# ethernetGateway.net
KiCad netlist of a schematic drawn in EAGLE
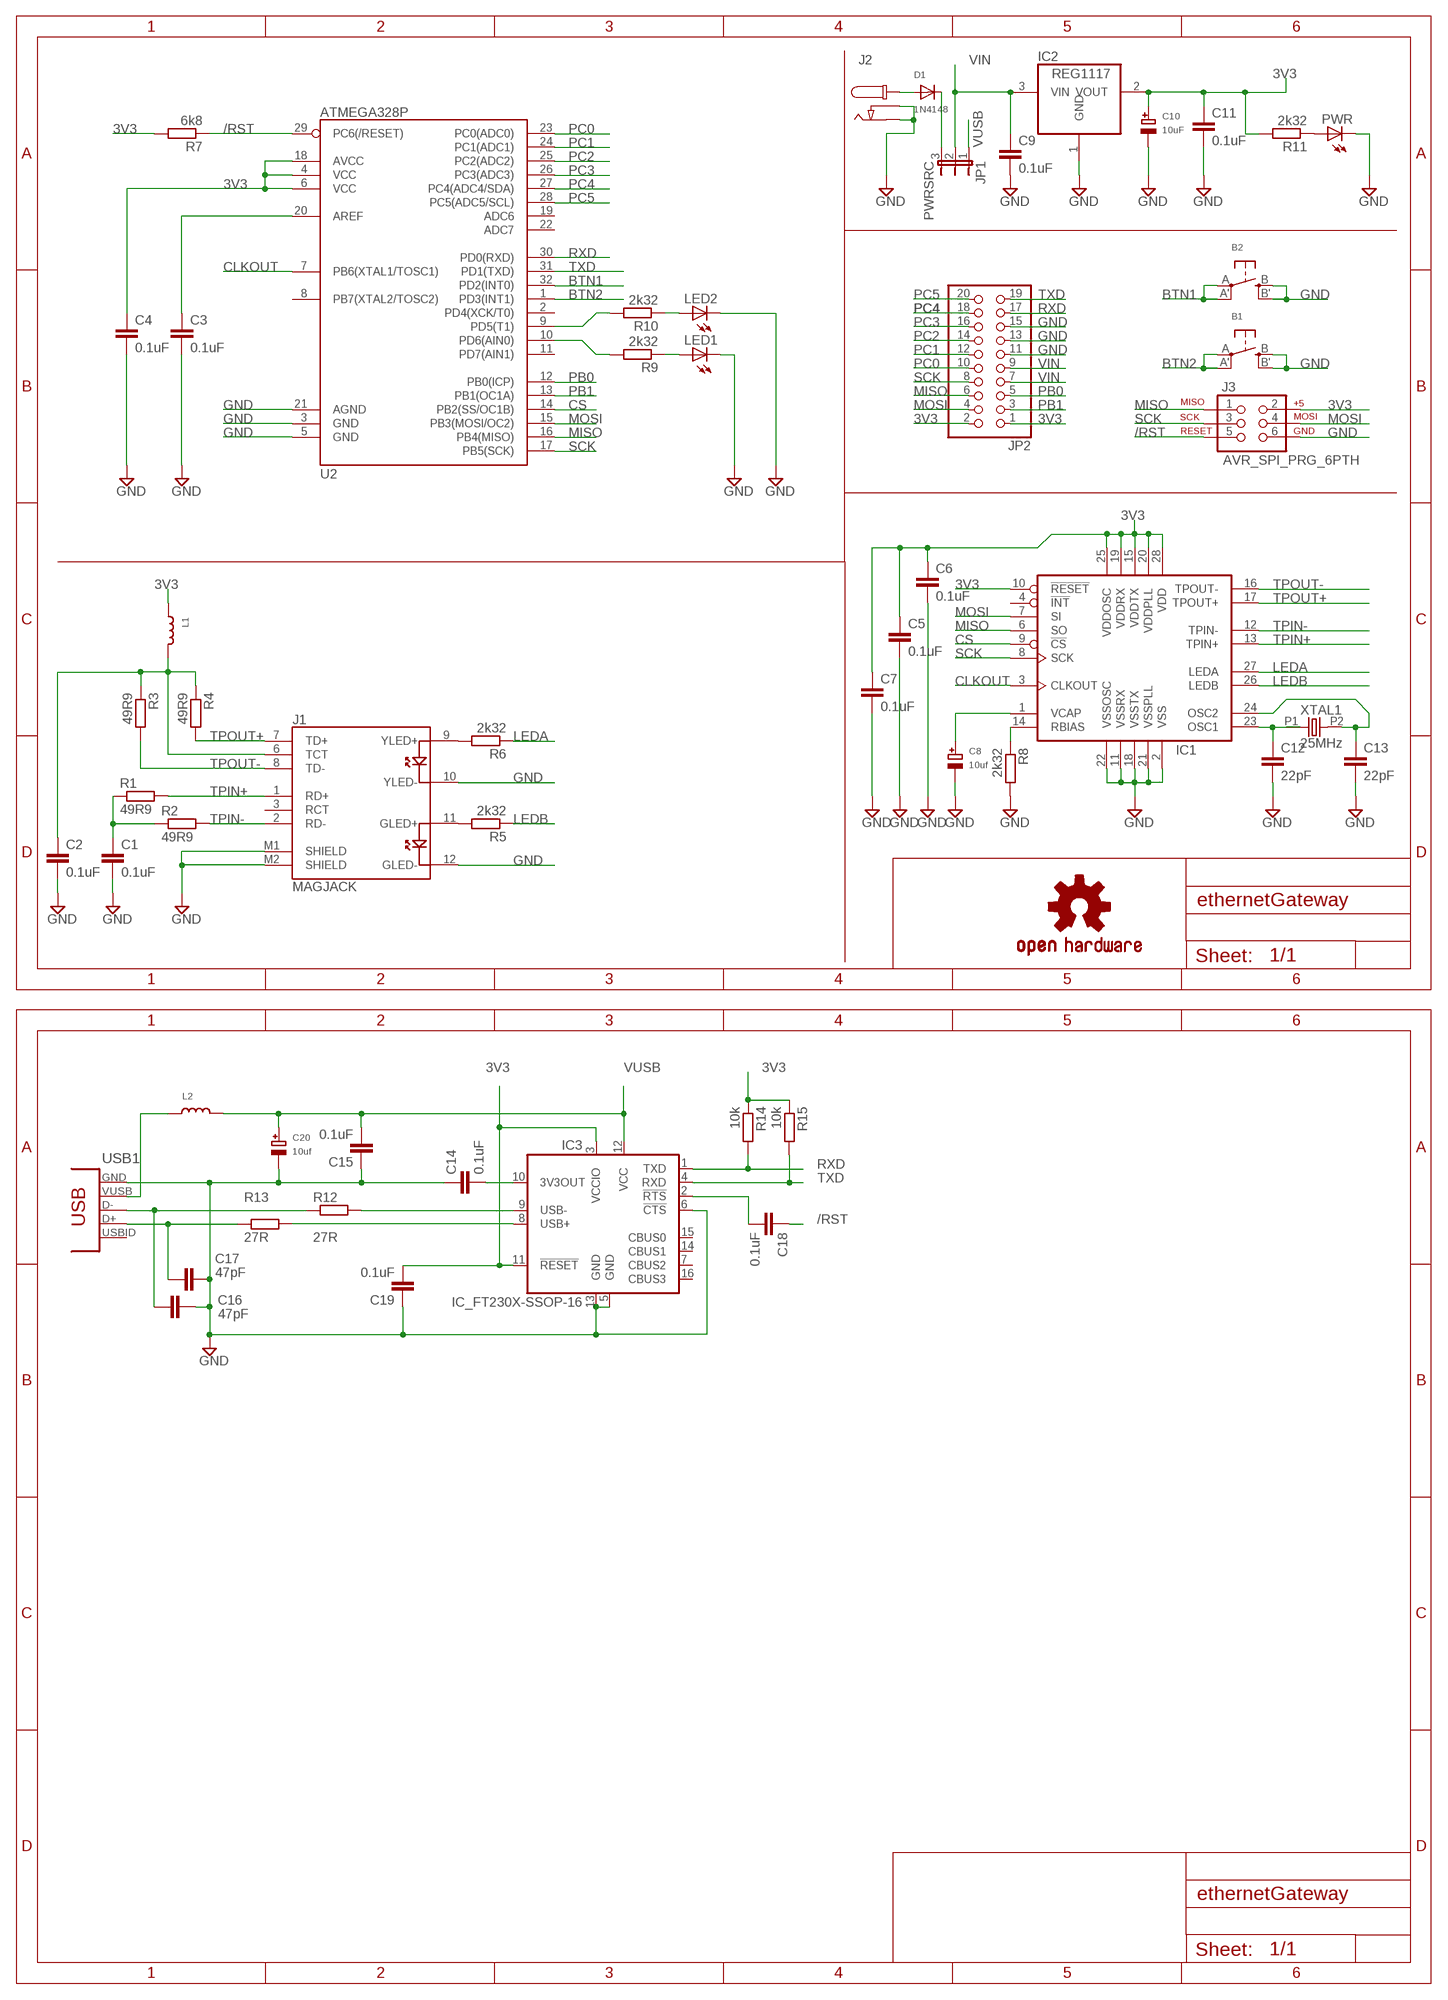
[diagram p0: schematic, sheet 1]

(export (version "E")
  (design (tool "Eeschema 10.0.6"))
  (components
    (comp (ref "B1")
      (value "SWITCH_TACT_SMT4.6X2.8")
      (footprint "eagle-import:BTN_KMR2_4.6X2.8")
      (libsource (lib "eagle-import") (part "SWITCH_TACT_SMT4.6X2.8"))
    )
    (comp (ref "B2")
      (value "SWITCH_TACT_SMT4.6X2.8")
      (footprint "eagle-import:BTN_KMR2_4.6X2.8")
      (libsource (lib "eagle-import") (part "SWITCH_TACT_SMT4.6X2.8"))
    )
    (comp (ref "C1")
      (value "0.1uF")
      (footprint "eagle-import:C0805")
      (libsource (lib "eagle-import") (part "C-EUC0805"))
    )
    (comp (ref "C2")
      (value "0.1uF")
      (footprint "eagle-import:C0805")
      (libsource (lib "eagle-import") (part "C-EUC0805"))
    )
    (comp (ref "C3")
      (value "0.1uF")
      (footprint "eagle-import:C0805")
      (libsource (lib "eagle-import") (part "C-EUC0805"))
    )
    (comp (ref "C4")
      (value "0.1uF")
      (footprint "eagle-import:C0805")
      (libsource (lib "eagle-import") (part "C-EUC0805"))
    )
    (comp (ref "C5")
      (value "0.1uF")
      (footprint "eagle-import:C0805")
      (libsource (lib "eagle-import") (part "C-EUC0805"))
    )
    (comp (ref "C6")
      (value "0.1uF")
      (footprint "eagle-import:C0805")
      (libsource (lib "eagle-import") (part "C-EUC0805"))
    )
    (comp (ref "C7")
      (value "0.1uF")
      (footprint "eagle-import:C0805")
      (libsource (lib "eagle-import") (part "C-EUC0805"))
    )
    (comp (ref "C8")
      (value "10uf")
      (footprint "eagle-import:EIA7343-31_D-R")
      (libsource (lib "eagle-import") (part "CAP_TANTALUMD/7343_REFLOW"))
    )
    (comp (ref "C9")
      (value "0.1uF")
      (footprint "eagle-import:C0805")
      (libsource (lib "eagle-import") (part "C-EUC0805"))
    )
    (comp (ref "C10")
      (value "10uF")
      (footprint "eagle-import:EIA7343-31_D-R")
      (libsource (lib "eagle-import") (part "CAP_TANTALUMD/7343_REFLOW"))
    )
    (comp (ref "C11")
      (value "0.1uF")
      (footprint "eagle-import:C0805")
      (libsource (lib "eagle-import") (part "C-EUC0805"))
    )
    (comp (ref "C12")
      (value "22pF")
      (footprint "eagle-import:C0805")
      (libsource (lib "eagle-import") (part "C-EUC0805"))
    )
    (comp (ref "C13")
      (value "22pF")
      (footprint "eagle-import:C0805")
      (libsource (lib "eagle-import") (part "C-EUC0805"))
    )
    (comp (ref "C14")
      (value "0.1uF")
      (footprint "eagle-import:C0805")
      (libsource (lib "eagle-import") (part "C-EUC0805"))
    )
    (comp (ref "C15")
      (value "0.1uF")
      (footprint "eagle-import:C0805")
      (libsource (lib "eagle-import") (part "C-EUC0805"))
    )
    (comp (ref "C16")
      (value "47pF")
      (footprint "eagle-import:C0805")
      (libsource (lib "eagle-import") (part "C-EUC0805"))
    )
    (comp (ref "C17")
      (value "47pF")
      (footprint "eagle-import:C0805")
      (libsource (lib "eagle-import") (part "C-EUC0805"))
    )
    (comp (ref "C18")
      (value "0.1uF")
      (footprint "eagle-import:C0805")
      (libsource (lib "eagle-import") (part "C-EUC0805"))
    )
    (comp (ref "C19")
      (value "0.1uF")
      (footprint "eagle-import:C0805")
      (libsource (lib "eagle-import") (part "C-EUC0805"))
    )
    (comp (ref "C20")
      (value "10uf")
      (footprint "eagle-import:EIA7343-31_D-R")
      (libsource (lib "eagle-import") (part "CAP_TANTALUMD/7343_REFLOW"))
    )
    (comp (ref "D1")
      (value "1N4148")
      (footprint "eagle-import:SMADIODE")
      (libsource (lib "eagle-import") (part "DIODESMA"))
    )
    (comp (ref "IC1")
      (value "IC_ENC28J60-SOIC-28")
      (footprint "eagle-import:SOIC-28W")
      (libsource (lib "eagle-import") (part "IC_ENC28J60-SOIC-28"))
    )
    (comp (ref "IC2")
      (value "REG1117")
      (footprint "eagle-import:SOT223")
      (libsource (lib "eagle-import") (part "REG1117"))
    )
    (comp (ref "IC3")
      (value "IC_FT230X-SSOP-16")
      (footprint "eagle-import:SSOP-16-FTDI")
      (libsource (lib "eagle-import") (part "IC_FT230X-SSOP-16"))
    )
    (comp (ref "J1")
      (value "MAGJACK")
      (footprint "eagle-import:MAGJACK")
      (libsource (lib "eagle-import") (part "MAGJACK"))
    )
    (comp (ref "J2")
      (value "CON_DC_M-DC_PTH")
      (footprint "eagle-import:DC_BARREL_JACK_PTH_2MM")
      (libsource (lib "eagle-import") (part "CON_DC_M-DC_PTH"))
    )
    (comp (ref "J3")
      (value "AVR_SPI_PRG_6PTH")
      (footprint "eagle-import:2X3")
      (libsource (lib "eagle-import") (part "AVR_SPI_PRG_6PTH"))
    )
    (comp (ref "JP1")
      (value "PWRSRC")
      (footprint "eagle-import:JP2W")
      (libsource (lib "eagle-import") (part "JP2W"))
    )
    (comp (ref "JP2")
      (value "PINHD-2X10")
      (footprint "eagle-import:2X10")
      (libsource (lib "eagle-import") (part "PINHD-2X10"))
    )
    (comp (ref "L1")
      (value "INDUCTOR0805")
      (footprint "eagle-import:0805")
      (libsource (lib "eagle-import") (part "INDUCTOR0805"))
    )
    (comp (ref "L2")
      (value "INDUCTOR0805")
      (footprint "eagle-import:0805")
      (libsource (lib "eagle-import") (part "INDUCTOR0805"))
    )
    (comp (ref "LED1")
      (value "LED-0805")
      (footprint "eagle-import:LED-805")
      (libsource (lib "eagle-import") (part "LED-0805"))
    )
    (comp (ref "LED2")
      (value "LED-0805")
      (footprint "eagle-import:LED-805")
      (libsource (lib "eagle-import") (part "LED-0805"))
    )
    (comp (ref "LOGO1")
      (value "OSHW-LOGOL")
      (footprint "eagle-import:OSHW-LOGO-L")
      (libsource (lib "eagle-import") (part "OSHW-LOGOL"))
    )
    (comp (ref "PWR")
      (value "LED-0805")
      (footprint "eagle-import:LED-805")
      (libsource (lib "eagle-import") (part "LED-0805"))
    )
    (comp (ref "R1")
      (value "49R9")
      (footprint "eagle-import:R0805")
      (libsource (lib "eagle-import") (part "R-EU_R0805"))
    )
    (comp (ref "R2")
      (value "49R9")
      (footprint "eagle-import:R0805")
      (libsource (lib "eagle-import") (part "R-EU_R0805"))
    )
    (comp (ref "R3")
      (value "49R9")
      (footprint "eagle-import:R0805")
      (libsource (lib "eagle-import") (part "R-EU_R0805"))
    )
    (comp (ref "R4")
      (value "49R9")
      (footprint "eagle-import:R0805")
      (libsource (lib "eagle-import") (part "R-EU_R0805"))
    )
    (comp (ref "R5")
      (value "2k32")
      (footprint "eagle-import:R0805")
      (libsource (lib "eagle-import") (part "R-EU_R0805"))
    )
    (comp (ref "R6")
      (value "2k32")
      (footprint "eagle-import:R0805")
      (libsource (lib "eagle-import") (part "R-EU_R0805"))
    )
    (comp (ref "R7")
      (value "6k8")
      (footprint "eagle-import:R0805")
      (libsource (lib "eagle-import") (part "R-EU_R0805"))
    )
    (comp (ref "R8")
      (value "2k32")
      (footprint "eagle-import:R0805")
      (libsource (lib "eagle-import") (part "R-EU_R0805"))
    )
    (comp (ref "R9")
      (value "2k32")
      (footprint "eagle-import:R0805")
      (libsource (lib "eagle-import") (part "R-EU_R0805"))
    )
    (comp (ref "R10")
      (value "2k32")
      (footprint "eagle-import:R0805")
      (libsource (lib "eagle-import") (part "R-EU_R0805"))
    )
    (comp (ref "R11")
      (value "2k32")
      (footprint "eagle-import:R0805")
      (libsource (lib "eagle-import") (part "R-EU_R0805"))
    )
    (comp (ref "R12")
      (value "27R")
      (footprint "eagle-import:M0805")
      (libsource (lib "eagle-import") (part "R-EU_M0805"))
    )
    (comp (ref "R13")
      (value "27R")
      (footprint "eagle-import:M0805")
      (libsource (lib "eagle-import") (part "R-EU_M0805"))
    )
    (comp (ref "R14")
      (value "10k")
      (footprint "eagle-import:R0805")
      (libsource (lib "eagle-import") (part "R-EU_R0805"))
    )
    (comp (ref "R15")
      (value "10k")
      (footprint "eagle-import:R0805")
      (libsource (lib "eagle-import") (part "R-EU_R0805"))
    )
    (comp (ref "U2")
      (value "ATMEGA328P")
      (footprint "eagle-import:TQFP32-08")
      (libsource (lib "eagle-import") (part "ATMEGA328_SMT"))
    )
    (comp (ref "USB1")
      (value "CON-USB-F-MINI-B")
      (footprint "eagle-import:CONN_USB_MINI-B")
      (libsource (lib "eagle-import") (part "CON-USB-F-MINI-B"))
    )
    (comp (ref "XTAL1")
      (value "25MHz")
      (footprint "eagle-import:HC-49U-PTH")
      (libsource (lib "eagle-import") (part "OSC-XTAL-HC-49U-PTH"))
    )
  )
  (nets
    (net (code "1") (name "/3V3") (class "Default")
      (node (ref "C10") (pin "+") (pinfunction "+_+") (pintype "passive"))
      (node (ref "C11") (pin "1") (pinfunction "1_1") (pintype "passive"))
      (node (ref "C19") (pin "2") (pinfunction "2_2") (pintype "passive"))
      (node (ref "C4") (pin "1") (pinfunction "1_1") (pintype "passive"))
      (node (ref "C5") (pin "1") (pinfunction "1_1") (pintype "passive"))
      (node (ref "C6") (pin "1") (pinfunction "1_1") (pintype "passive"))
      (node (ref "C7") (pin "1") (pinfunction "1_1") (pintype "passive"))
      (node (ref "IC1") (pin "10") (pinfunction "~{RESET}_10") (pintype "input"))
      (node (ref "IC1") (pin "15") (pinfunction "VDDTX_15") (pintype "power_in"))
      (node (ref "IC1") (pin "19") (pinfunction "VDDRX_19") (pintype "power_in"))
      (node (ref "IC1") (pin "20") (pinfunction "VDDPLL_20") (pintype "power_in"))
      (node (ref "IC1") (pin "25") (pinfunction "VDDOSC_25") (pintype "power_in"))
      (node (ref "IC1") (pin "28") (pinfunction "VDD_28") (pintype "power_in"))
      (node (ref "IC2") (pin "2") (pinfunction "VOUT_2") (pintype "output"))
      (node (ref "IC3") (pin "11") (pinfunction "~{RESET}_11") (pintype "bidirectional"))
      (node (ref "IC3") (pin "3") (pinfunction "VCCIO_3") (pintype "power_in"))
      (node (ref "J3") (pin "2") (pinfunction "2_2") (pintype "passive"))
      (node (ref "JP2") (pin "1") (pinfunction "1_1") (pintype "passive"))
      (node (ref "JP2") (pin "2") (pinfunction "2_2") (pintype "passive"))
      (node (ref "L1") (pin "1") (pinfunction "1_1") (pintype "passive"))
      (node (ref "R11") (pin "2") (pinfunction "2_2") (pintype "passive"))
      (node (ref "R14") (pin "1") (pinfunction "1_1") (pintype "passive"))
      (node (ref "R15") (pin "1") (pinfunction "1_1") (pintype "passive"))
      (node (ref "R7") (pin "2") (pinfunction "2_2") (pintype "passive"))
      (node (ref "U2") (pin "18") (pinfunction "AVCC_18") (pintype "bidirectional"))
      (node (ref "U2") (pin "4") (pinfunction "VCC_4") (pintype "bidirectional"))
      (node (ref "U2") (pin "6") (pinfunction "VCC_6") (pintype "bidirectional"))
    )
    (net (code "2") (name "/BTN1") (class "Default")
      (node (ref "B2") (pin "A") (pinfunction "P_A") (pintype "passive"))
      (node (ref "B2") (pin "A'") (pinfunction "P1_A'") (pintype "passive"))
      (node (ref "U2") (pin "32") (pinfunction "PD2(INT0)_32") (pintype "bidirectional"))
    )
    (net (code "3") (name "/BTN2") (class "Default")
      (node (ref "B1") (pin "A") (pinfunction "P_A") (pintype "passive"))
      (node (ref "B1") (pin "A'") (pinfunction "P1_A'") (pintype "passive"))
      (node (ref "U2") (pin "1") (pinfunction "PD3(INT1)_1") (pintype "bidirectional"))
    )
    (net (code "4") (name "/CLKOUT") (class "Default")
      (node (ref "IC1") (pin "3") (pinfunction "CLKOUT_3") (pintype "output"))
      (node (ref "U2") (pin "7") (pinfunction "PB6(XTAL1/TOSC1)_7") (pintype "bidirectional"))
    )
    (net (code "5") (name "/CS") (class "Default")
      (node (ref "IC1") (pin "9") (pinfunction "~{CS}_9") (pintype "input"))
      (node (ref "U2") (pin "14") (pinfunction "PB2(SS/OC1B)_14") (pintype "bidirectional"))
    )
    (net (code "6") (name "/LEDA") (class "Default")
      (node (ref "IC1") (pin "27") (pinfunction "LEDA_27") (pintype "output"))
      (node (ref "R6") (pin "1") (pinfunction "1_1") (pintype "passive"))
    )
    (net (code "7") (name "/LEDB") (class "Default")
      (node (ref "IC1") (pin "26") (pinfunction "LEDB_26") (pintype "output"))
      (node (ref "R5") (pin "1") (pinfunction "1_1") (pintype "passive"))
    )
    (net (code "8") (name "/MISO") (class "Default")
      (node (ref "IC1") (pin "6") (pinfunction "SO_6") (pintype "output"))
      (node (ref "J3") (pin "1") (pinfunction "1_1") (pintype "passive"))
      (node (ref "JP2") (pin "6") (pinfunction "6_6") (pintype "passive"))
      (node (ref "U2") (pin "16") (pinfunction "PB4(MISO)_16") (pintype "bidirectional"))
    )
    (net (code "9") (name "/MOSI") (class "Default")
      (node (ref "IC1") (pin "7") (pinfunction "SI_7") (pintype "input"))
      (node (ref "J3") (pin "4") (pinfunction "4_4") (pintype "passive"))
      (node (ref "JP2") (pin "4") (pinfunction "4_4") (pintype "passive"))
      (node (ref "U2") (pin "15") (pinfunction "PB3(MOSI/OC2)_15") (pintype "bidirectional"))
    )
    (net (code "10") (name "/PB0") (class "Default")
      (node (ref "JP2") (pin "5") (pinfunction "5_5") (pintype "passive"))
      (node (ref "U2") (pin "12") (pinfunction "PB0(ICP)_12") (pintype "bidirectional"))
    )
    (net (code "11") (name "/PB1") (class "Default")
      (node (ref "JP2") (pin "3") (pinfunction "3_3") (pintype "passive"))
      (node (ref "U2") (pin "13") (pinfunction "PB1(OC1A)_13") (pintype "bidirectional"))
    )
    (net (code "12") (name "/PC0") (class "Default")
      (node (ref "JP2") (pin "10") (pinfunction "10_10") (pintype "passive"))
      (node (ref "U2") (pin "23") (pinfunction "PC0(ADC0)_23") (pintype "bidirectional"))
    )
    (net (code "13") (name "/PC1") (class "Default")
      (node (ref "JP2") (pin "12") (pinfunction "12_12") (pintype "passive"))
      (node (ref "U2") (pin "24") (pinfunction "PC1(ADC1)_24") (pintype "bidirectional"))
    )
    (net (code "14") (name "/PC2") (class "Default")
      (node (ref "JP2") (pin "14") (pinfunction "14_14") (pintype "passive"))
      (node (ref "U2") (pin "25") (pinfunction "PC2(ADC2)_25") (pintype "bidirectional"))
    )
    (net (code "15") (name "/PC3") (class "Default")
      (node (ref "JP2") (pin "16") (pinfunction "16_16") (pintype "passive"))
      (node (ref "U2") (pin "26") (pinfunction "PC3(ADC3)_26") (pintype "bidirectional"))
    )
    (net (code "16") (name "/PC4") (class "Default")
      (node (ref "JP2") (pin "18") (pinfunction "18_18") (pintype "passive"))
      (node (ref "U2") (pin "27") (pinfunction "PC4(ADC4/SDA)_27") (pintype "bidirectional"))
    )
    (net (code "17") (name "/PC5") (class "Default")
      (node (ref "JP2") (pin "20") (pinfunction "20_20") (pintype "passive"))
      (node (ref "U2") (pin "28") (pinfunction "PC5(ADC5/SCL)_28") (pintype "bidirectional"))
    )
    (net (code "18") (name "/RXD") (class "Default")
      (node (ref "IC3") (pin "1") (pinfunction "TXD_1") (pintype "output"))
      (node (ref "JP2") (pin "17") (pinfunction "17_17") (pintype "passive"))
      (node (ref "R14") (pin "2") (pinfunction "2_2") (pintype "passive"))
      (node (ref "U2") (pin "30") (pinfunction "PD0(RXD)_30") (pintype "bidirectional"))
    )
    (net (code "19") (name "/SCK") (class "Default")
      (node (ref "IC1") (pin "8") (pinfunction "SCK_8") (pintype "input"))
      (node (ref "J3") (pin "3") (pinfunction "3_3") (pintype "passive"))
      (node (ref "JP2") (pin "8") (pinfunction "8_8") (pintype "passive"))
      (node (ref "U2") (pin "17") (pinfunction "PB5(SCK)_17") (pintype "bidirectional"))
    )
    (net (code "20") (name "/TPIN+") (class "Default")
      (node (ref "IC1") (pin "13") (pinfunction "TPIN+_13") (pintype "input"))
      (node (ref "J1") (pin "1") (pinfunction "RD+_1") (pintype "bidirectional"))
      (node (ref "R1") (pin "2") (pinfunction "2_2") (pintype "passive"))
    )
    (net (code "21") (name "/TPIN-") (class "Default")
      (node (ref "IC1") (pin "12") (pinfunction "TPIN-_12") (pintype "input"))
      (node (ref "J1") (pin "2") (pinfunction "RD-_2") (pintype "bidirectional"))
      (node (ref "R2") (pin "2") (pinfunction "2_2") (pintype "passive"))
    )
    (net (code "22") (name "/TPOUT+") (class "Default")
      (node (ref "IC1") (pin "17") (pinfunction "TPOUT+_17") (pintype "output"))
      (node (ref "J1") (pin "7") (pinfunction "TD+_7") (pintype "bidirectional"))
      (node (ref "R4") (pin "2") (pinfunction "2_2") (pintype "passive"))
    )
    (net (code "23") (name "/TPOUT-") (class "Default")
      (node (ref "IC1") (pin "16") (pinfunction "TPOUT-_16") (pintype "output"))
      (node (ref "J1") (pin "8") (pinfunction "TD-_8") (pintype "bidirectional"))
      (node (ref "R3") (pin "2") (pinfunction "2_2") (pintype "passive"))
    )
    (net (code "24") (name "/TXD") (class "Default")
      (node (ref "IC3") (pin "4") (pinfunction "RXD_4") (pintype "input"))
      (node (ref "JP2") (pin "19") (pinfunction "19_19") (pintype "passive"))
      (node (ref "R15") (pin "2") (pinfunction "2_2") (pintype "passive"))
      (node (ref "U2") (pin "31") (pinfunction "PD1(TXD)_31") (pintype "bidirectional"))
    )
    (net (code "25") (name "/VIN") (class "Default")
      (node (ref "C9") (pin "1") (pinfunction "1_1") (pintype "passive"))
      (node (ref "IC2") (pin "3") (pinfunction "VIN_3") (pintype "input"))
      (node (ref "JP1") (pin "2") (pinfunction "2_2") (pintype "passive"))
      (node (ref "JP2") (pin "7") (pinfunction "7_7") (pintype "passive"))
      (node (ref "JP2") (pin "9") (pinfunction "9_9") (pintype "passive"))
    )
    (net (code "26") (name "/VUSB") (class "Default")
      (node (ref "C15") (pin "2") (pinfunction "2_2") (pintype "passive"))
      (node (ref "C20") (pin "+") (pinfunction "+_+") (pintype "passive"))
      (node (ref "IC3") (pin "12") (pinfunction "VCC_12") (pintype "power_in"))
      (node (ref "JP1") (pin "1") (pinfunction "1_1") (pintype "passive"))
      (node (ref "L2") (pin "2") (pinfunction "2_2") (pintype "passive"))
    )
    (net (code "27") (name "/{slash}RST") (class "Default")
      (node (ref "C18") (pin "1") (pinfunction "1_1") (pintype "passive"))
      (node (ref "J3") (pin "5") (pinfunction "5_5") (pintype "passive"))
      (node (ref "R7") (pin "1") (pinfunction "1_1") (pintype "passive"))
      (node (ref "U2") (pin "29") (pinfunction "PC6(/RESET)_29") (pintype "bidirectional"))
    )
    (net (code "28") (name "GND") (class "Default")
      (node (ref "B1") (pin "B") (pinfunction "S_B") (pintype "passive"))
      (node (ref "B1") (pin "B'") (pinfunction "S1_B'") (pintype "passive"))
      (node (ref "B2") (pin "B") (pinfunction "S_B") (pintype "passive"))
      (node (ref "B2") (pin "B'") (pinfunction "S1_B'") (pintype "passive"))
      (node (ref "C1") (pin "2") (pinfunction "2_2") (pintype "passive"))
      (node (ref "C10") (pin "-") (pinfunction "-_-") (pintype "passive"))
      (node (ref "C11") (pin "2") (pinfunction "2_2") (pintype "passive"))
      (node (ref "C12") (pin "2") (pinfunction "2_2") (pintype "passive"))
      (node (ref "C13") (pin "2") (pinfunction "2_2") (pintype "passive"))
      (node (ref "C14") (pin "1") (pinfunction "1_1") (pintype "passive"))
      (node (ref "C15") (pin "1") (pinfunction "1_1") (pintype "passive"))
      (node (ref "C16") (pin "1") (pinfunction "1_1") (pintype "passive"))
      (node (ref "C17") (pin "2") (pinfunction "2_2") (pintype "passive"))
      (node (ref "C19") (pin "1") (pinfunction "1_1") (pintype "passive"))
      (node (ref "C2") (pin "2") (pinfunction "2_2") (pintype "passive"))
      (node (ref "C20") (pin "-") (pinfunction "-_-") (pintype "passive"))
      (node (ref "C3") (pin "2") (pinfunction "2_2") (pintype "passive"))
      (node (ref "C4") (pin "2") (pinfunction "2_2") (pintype "passive"))
      (node (ref "C5") (pin "2") (pinfunction "2_2") (pintype "passive"))
      (node (ref "C6") (pin "2") (pinfunction "2_2") (pintype "passive"))
      (node (ref "C7") (pin "2") (pinfunction "2_2") (pintype "passive"))
      (node (ref "C8") (pin "-") (pinfunction "-_-") (pintype "passive"))
      (node (ref "C9") (pin "2") (pinfunction "2_2") (pintype "passive"))
      (node (ref "IC1") (pin "11") (pinfunction "VSSRX_11") (pintype "power_in"))
      (node (ref "IC1") (pin "18") (pinfunction "VSSTX_18") (pintype "power_in"))
      (node (ref "IC1") (pin "2") (pinfunction "VSS_2") (pintype "power_in"))
      (node (ref "IC1") (pin "21") (pinfunction "VSSPLL_21") (pintype "power_in"))
      (node (ref "IC1") (pin "22") (pinfunction "VSSOSC_22") (pintype "power_in"))
      (node (ref "IC2") (pin "1") (pinfunction "GND_1") (pintype "power_in"))
      (node (ref "IC3") (pin "13") (pinfunction "GND_13") (pintype "power_in"))
      (node (ref "IC3") (pin "5") (pinfunction "GND_5") (pintype "power_in"))
      (node (ref "IC3") (pin "6") (pinfunction "~{CTS}_6") (pintype "bidirectional"))
      (node (ref "J1") (pin "10") (pinfunction "YLED-_10") (pintype "bidirectional"))
      (node (ref "J1") (pin "12") (pinfunction "GLED-_12") (pintype "bidirectional"))
      (node (ref "J1") (pin "M1") (pinfunction "SHIELD_M1") (pintype "bidirectional"))
      (node (ref "J1") (pin "M2") (pinfunction "SHIELD_M2") (pintype "bidirectional"))
      (node (ref "J2") (pin "P2") (pinfunction "P3_P2") (pintype "passive"))
      (node (ref "J2") (pin "P3") (pinfunction "P2_P3") (pintype "passive"))
      (node (ref "J3") (pin "6") (pinfunction "6_6") (pintype "passive"))
      (node (ref "JP2") (pin "11") (pinfunction "11_11") (pintype "passive"))
      (node (ref "JP2") (pin "13") (pinfunction "13_13") (pintype "passive"))
      (node (ref "JP2") (pin "15") (pinfunction "15_15") (pintype "passive"))
      (node (ref "LED1") (pin "C") (pinfunction "C_C") (pintype "passive"))
      (node (ref "LED2") (pin "C") (pinfunction "C_C") (pintype "passive"))
      (node (ref "PWR") (pin "C") (pinfunction "C_C") (pintype "passive"))
      (node (ref "R8") (pin "2") (pinfunction "2_2") (pintype "passive"))
      (node (ref "U2") (pin "21") (pinfunction "AGND_21") (pintype "bidirectional"))
      (node (ref "U2") (pin "3") (pinfunction "GND_3") (pintype "bidirectional"))
      (node (ref "U2") (pin "5") (pinfunction "GND_5") (pintype "bidirectional"))
      (node (ref "USB1") (pin "GND") (pinfunction "GND_GND") (pintype "bidirectional"))
    )
    (net (code "29") (name "Net-(C1-Pad1)") (class "Default")
      (node (ref "C1") (pin "1") (pinfunction "1_1") (pintype "passive"))
      (node (ref "R1") (pin "1") (pinfunction "1_1") (pintype "passive"))
      (node (ref "R2") (pin "1") (pinfunction "1_1") (pintype "passive"))
    )
    (net (code "30") (name "Net-(C16-Pad2)") (class "Default")
      (node (ref "C16") (pin "2") (pinfunction "2_2") (pintype "passive"))
      (node (ref "R12") (pin "1") (pinfunction "1_1") (pintype "passive"))
      (node (ref "USB1") (pin "D-") (pinfunction "D-_D-") (pintype "bidirectional"))
    )
    (net (code "31") (name "Net-(C17-Pad1)") (class "Default")
      (node (ref "C17") (pin "1") (pinfunction "1_1") (pintype "passive"))
      (node (ref "R13") (pin "1") (pinfunction "1_1") (pintype "passive"))
      (node (ref "USB1") (pin "D+") (pinfunction "D+_D+") (pintype "bidirectional"))
    )
    (net (code "32") (name "Net-(D1-PadA)") (class "Default")
      (node (ref "D1") (pin "A") (pinfunction "A_A") (pintype "passive"))
      (node (ref "J2") (pin "P1") (pinfunction "P1_P1") (pintype "passive"))
    )
    (net (code "33") (name "Net-(D1-PadC)") (class "Default")
      (node (ref "D1") (pin "C") (pinfunction "C_C") (pintype "passive"))
      (node (ref "JP1") (pin "3") (pinfunction "3_3") (pintype "passive"))
    )
    (net (code "34") (name "Net-(IC1-OSC1)") (class "Default")
      (node (ref "C12") (pin "1") (pinfunction "1_1") (pintype "passive"))
      (node (ref "IC1") (pin "23") (pinfunction "OSC1_23") (pintype "input"))
      (node (ref "XTAL1") (pin "P1") (pinfunction "1_P1") (pintype "passive"))
    )
    (net (code "35") (name "Net-(IC1-OSC2)") (class "Default")
      (node (ref "C13") (pin "1") (pinfunction "1_1") (pintype "passive"))
      (node (ref "IC1") (pin "24") (pinfunction "OSC2_24") (pintype "output"))
      (node (ref "XTAL1") (pin "P2") (pinfunction "2_P2") (pintype "passive"))
    )
    (net (code "36") (name "Net-(IC1-RBIAS)") (class "Default")
      (node (ref "IC1") (pin "14") (pinfunction "RBIAS_14") (pintype "input"))
      (node (ref "R8") (pin "1") (pinfunction "1_1") (pintype "passive"))
    )
    (net (code "37") (name "Net-(IC1-VCAP)") (class "Default")
      (node (ref "C8") (pin "+") (pinfunction "+_+") (pintype "passive"))
      (node (ref "IC1") (pin "1") (pinfunction "VCAP_1") (pintype "input"))
    )
    (net (code "38") (name "Net-(IC3-3V3OUT)") (class "Default")
      (node (ref "C14") (pin "2") (pinfunction "2_2") (pintype "passive"))
      (node (ref "IC3") (pin "10") (pinfunction "3V3OUT_10") (pintype "power_in"))
    )
    (net (code "39") (name "Net-(IC3-USB+)") (class "Default")
      (node (ref "IC3") (pin "8") (pinfunction "USB+_8") (pintype "output"))
      (node (ref "R13") (pin "2") (pinfunction "2_2") (pintype "passive"))
    )
    (net (code "40") (name "Net-(IC3-USB-)") (class "Default")
      (node (ref "IC3") (pin "9") (pinfunction "USB-_9") (pintype "input"))
      (node (ref "R12") (pin "2") (pinfunction "2_2") (pintype "passive"))
    )
    (net (code "41") (name "Net-(IC3-~{RTS})") (class "Default")
      (node (ref "C18") (pin "2") (pinfunction "2_2") (pintype "passive"))
      (node (ref "IC3") (pin "2") (pinfunction "~{RTS}_2") (pintype "bidirectional"))
    )
    (net (code "42") (name "Net-(J1-GLED+)") (class "Default")
      (node (ref "J1") (pin "11") (pinfunction "GLED+_11") (pintype "bidirectional"))
      (node (ref "R5") (pin "2") (pinfunction "2_2") (pintype "passive"))
    )
    (net (code "43") (name "Net-(J1-TCT)") (class "Default")
      (node (ref "C2") (pin "1") (pinfunction "1_1") (pintype "passive"))
      (node (ref "J1") (pin "6") (pinfunction "TCT_6") (pintype "bidirectional"))
      (node (ref "L1") (pin "2") (pinfunction "2_2") (pintype "passive"))
      (node (ref "R3") (pin "1") (pinfunction "1_1") (pintype "passive"))
      (node (ref "R4") (pin "1") (pinfunction "1_1") (pintype "passive"))
    )
    (net (code "44") (name "Net-(J1-YLED+)") (class "Default")
      (node (ref "J1") (pin "9") (pinfunction "YLED+_9") (pintype "bidirectional"))
      (node (ref "R6") (pin "2") (pinfunction "2_2") (pintype "passive"))
    )
    (net (code "45") (name "Net-(L2-Pad1)") (class "Default")
      (node (ref "L2") (pin "1") (pinfunction "1_1") (pintype "passive"))
      (node (ref "USB1") (pin "VUSB") (pinfunction "VUSB_VUSB") (pintype "bidirectional"))
    )
    (net (code "46") (name "Net-(LED1-PadA)") (class "Default")
      (node (ref "LED1") (pin "A") (pinfunction "A_A") (pintype "passive"))
      (node (ref "R9") (pin "1") (pinfunction "1_1") (pintype "passive"))
    )
    (net (code "47") (name "Net-(LED2-PadA)") (class "Default")
      (node (ref "LED2") (pin "A") (pinfunction "A_A") (pintype "passive"))
      (node (ref "R10") (pin "1") (pinfunction "1_1") (pintype "passive"))
    )
    (net (code "48") (name "Net-(PWR-PadA)") (class "Default")
      (node (ref "PWR") (pin "A") (pinfunction "A_A") (pintype "passive"))
      (node (ref "R11") (pin "1") (pinfunction "1_1") (pintype "passive"))
    )
    (net (code "49") (name "Net-(U2-AREF)") (class "Default")
      (node (ref "C3") (pin "1") (pinfunction "1_1") (pintype "passive"))
      (node (ref "U2") (pin "20") (pinfunction "AREF_20") (pintype "bidirectional"))
    )
    (net (code "50") (name "Net-(U2-PD5(T1))") (class "Default")
      (node (ref "R10") (pin "2") (pinfunction "2_2") (pintype "passive"))
      (node (ref "U2") (pin "9") (pinfunction "PD5(T1)_9") (pintype "bidirectional"))
    )
    (net (code "51") (name "Net-(U2-PD6(AIN0))") (class "Default")
      (node (ref "R9") (pin "2") (pinfunction "2_2") (pintype "passive"))
      (node (ref "U2") (pin "10") (pinfunction "PD6(AIN0)_10") (pintype "bidirectional"))
    )
    (net (code "52") (name "unconnected-(IC1-~{INT}-Pad4)") (class "Default")
      (node (ref "IC1") (pin "4") (pinfunction "~{INT}_4") (pintype "output"))
    )
    (net (code "53") (name "unconnected-(IC3-CBUS0-Pad15)") (class "Default")
      (node (ref "IC3") (pin "15") (pinfunction "CBUS0_15") (pintype "bidirectional"))
    )
    (net (code "54") (name "unconnected-(IC3-CBUS1-Pad14)") (class "Default")
      (node (ref "IC3") (pin "14") (pinfunction "CBUS1_14") (pintype "bidirectional"))
    )
    (net (code "55") (name "unconnected-(IC3-CBUS2-Pad7)") (class "Default")
      (node (ref "IC3") (pin "7") (pinfunction "CBUS2_7") (pintype "bidirectional"))
    )
    (net (code "56") (name "unconnected-(IC3-CBUS3-Pad16)") (class "Default")
      (node (ref "IC3") (pin "16") (pinfunction "CBUS3_16") (pintype "bidirectional"))
    )
    (net (code "57") (name "unconnected-(J1-RCT-Pad3)") (class "Default")
      (node (ref "J1") (pin "3") (pinfunction "RCT_3") (pintype "bidirectional"))
    )
    (net (code "58") (name "unconnected-(U2-ADC6-Pad19)") (class "Default")
      (node (ref "U2") (pin "19") (pinfunction "ADC6_19") (pintype "bidirectional"))
    )
    (net (code "59") (name "unconnected-(U2-ADC7-Pad22)") (class "Default")
      (node (ref "U2") (pin "22") (pinfunction "ADC7_22") (pintype "bidirectional"))
    )
    (net (code "60") (name "unconnected-(U2-PB7(XTAL2{slash}TOSC2)-Pad8)") (class "Default")
      (node (ref "U2") (pin "8") (pinfunction "PB7(XTAL2/TOSC2)_8") (pintype "bidirectional"))
    )
    (net (code "61") (name "unconnected-(U2-PD4(XCK{slash}T0)-Pad2)") (class "Default")
      (node (ref "U2") (pin "2") (pinfunction "PD4(XCK/T0)_2") (pintype "bidirectional"))
    )
    (net (code "62") (name "unconnected-(U2-PD7(AIN1)-Pad11)") (class "Default")
      (node (ref "U2") (pin "11") (pinfunction "PD7(AIN1)_11") (pintype "bidirectional"))
    )
    (net (code "63") (name "unconnected-(USB1B-USBID-PadID)") (class "Default")
      (node (ref "USB1") (pin "ID") (pinfunction "USBID_ID") (pintype "bidirectional"))
    )
  )
)
